# Spindle.net
KiCad netlist of a schematic drawn in Altium Designer
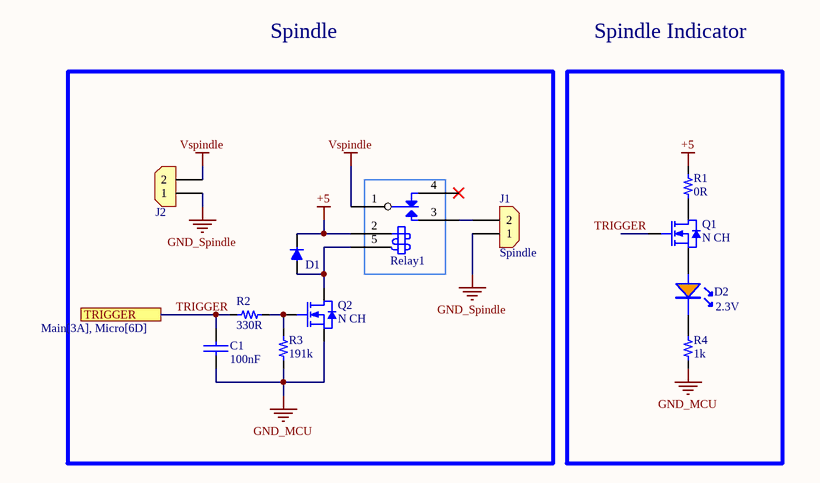
[diagram p0: Spindle.SchDoc]

(export (version "E")
  (design (tool "Eeschema 10.0.6"))
  (components
    (comp (ref "C1")
      (value "100nF")
      (footprint "0603_cap")
      (description "50V 100nF X7R ±10% 0603 Ceramic Capacitors RoHS")
      (fields
        (field (name "MANUFACTURER") "FOJAN")
        (field (name "MANUFACTURER PART NUMBER") "FCC0603B104K500CT")
      )
      (libsource (lib "CNCLib") (part "Cap_100nF_0603_50V"))
    )
    (comp (ref "D1")
      (value "DIODE STANDARD 50V 1A SOD-123F")
      (footprint "SOD-123FL_MCC")
      (description "25A Independent 50V 1.1V@1A 1A SOD-123F Single Diodes RoHS")
      (fields (field (name "MANUFACTURER") "YONGYUTAI") (field (name "MANUFACTURER PART NUMBER") "1N4001W"))
      (libsource (lib "CNCLib") (part "Diode 1N4001W"))
    )
    (comp (ref "D2")
      (value "2.3V")
      (footprint "0805_LED")
      (description "LED ORANGE WATER CLEAR 0805 SMD")
      (fields
        (field (name "MANUFACTURER") "XINGLIGHT")
        (field (name "MANUFACTURER PART NUMBER") "XL-2012UOC")
      )
      (libsource (lib "CNCLib") (part "LED_0805_Orange"))
    )
    (comp (ref "J1")
      (value "Connector 2pos")
      (footprint "CON_2x1_TH_5MM")
      (description "2POS 5MM")
      (fields (field (name "MANUFACTURER") "JILN") (field (name "MANUFACTURER PART NUMBER") "JL126-50002G01"))
      (libsource (lib "CNCLib") (part "Con_2x1_TH_5mm"))
    )
    (comp (ref "J2")
      (value "Connector 2pos")
      (footprint "CON_2x1_TH_5MM")
      (description "2POS 5MM")
      (fields (field (name "MANUFACTURER") "JILN") (field (name "MANUFACTURER PART NUMBER") "JL126-50002G01"))
      (libsource (lib "CNCLib") (part "Con_2x1_TH_5mm"))
    )
    (comp (ref "Q1")
      (value "N CH")
      (footprint "SOT_23_3")
      (description "MOSFET N-CH 50V 200mA SOT-23")
      (fields (field (name "MANUFACTURER") "onsemi") (field (name "MANUFACTURER PART NUMBER") "BSS138LT1G"))
      (libsource (lib "CNCLib") (part "Q_NFET_50V_200mA_SOT23"))
    )
    (comp (ref "Q2")
      (value "N CH")
      (footprint "SOT_23_3")
      (description "MOSFET N-CH 20V SOT23")
      (fields (field (name "MANUFACTURER") "Doeshare") (field (name "MANUFACTURER PART NUMBER") "DN2302S"))
      (libsource (lib "CNCLib") (part "Q_NFET_20V_3.2A_SOT23"))
    )
    (comp (ref "R1")
      (value "0R")
      (footprint "0603_res")
      (description "RES SMD 0R OHM 5% 1/10W 0603")
      (fields
        (field (name "MANUFACTURER") "FOJAN")
        (field (name "MANUFACTURER PART NUMBER") "FRC0603P000 TS")
      )
      (libsource (lib "CNCLib") (part "Res_0R_0603_1/10W"))
    )
    (comp (ref "R2")
      (value "330R")
      (footprint "0603_res")
      (description "RES SMD 330R OHM 5% 1/10W 0603")
      (fields
        (field (name "MANUFACTURER") "FOJAN")
        (field (name "MANUFACTURER PART NUMBER") "FRC0603J331 TS")
      )
      (libsource (lib "CNCLib") (part "Res_330R_0603_1/10W"))
    )
    (comp (ref "R3")
      (value "191k")
      (footprint "0603_res")
      (description "100mW Thick Film Resistor 75V ±100ppm/℃ ±1% 191kΩ 0603 Chip Resistor - Surface Mount ROHS")
      (fields
        (field (name "MANUFACTURER") "YAGEO")
        (field (name "MANUFACTURER PART NUMBER") "AC0603FR-07191KL")
      )
      (libsource (lib "CNCLib") (part "Res_191k_0603_1/10W"))
    )
    (comp (ref "R4")
      (value "1k")
      (footprint "0603_res")
      (description "RES SMD 1k OHM 5% 1/10W 0603")
      (fields
        (field (name "MANUFACTURER") "FOJAN")
        (field (name "MANUFACTURER PART NUMBER") "FRC0603J102 TS")
      )
      (libsource (lib "CNCLib") (part "Res_1k_0603_1/10W"))
    )
    (comp (ref "Relay1")
      (value "V_15A")
      (footprint "Relay_5V_15A")
      (description "250V@AC 5V 15A 1 Form C: 1C (SPDT-CO) Plugin,15.6x19.2mm Power Relays ROHS")
      (fields
        (field (name "MANUFACTURER") "Ningbo Songle Relay")
        (field (name "MANUFACTURER PART NUMBER") "SRD-05VDC-SL-C")
      )
      (libsource (lib "CNCLib") (part "Relay_5V_15A"))
    )
  )
  (nets
    (net (code "1") (name "+5") (class "Default")
      (node (ref "D1") (pin "2") (pinfunction "CATHODE_2") (pintype "passive"))
      (node (ref "R1") (pin "2") (pinfunction "2_2") (pintype "passive"))
      (node (ref "Relay1") (pin "2") (pinfunction "2_2") (pintype "passive"))
    )
    (net (code "2") (name "/TRIGGER") (class "Default")
      (node (ref "C1") (pin "1") (pinfunction "1_1") (pintype "passive"))
      (node (ref "Q1") (pin "1") (pinfunction "G_1") (pintype "passive"))
      (node (ref "R2") (pin "1") (pinfunction "1_1") (pintype "passive"))
    )
    (net (code "3") (name "GND_MCU") (class "Default")
      (node (ref "C1") (pin "2") (pinfunction "2_2") (pintype "passive"))
      (node (ref "Q2") (pin "2") (pinfunction "S_2") (pintype "passive"))
      (node (ref "R3") (pin "2") (pinfunction "2_2") (pintype "passive"))
      (node (ref "R4") (pin "1") (pinfunction "1_1") (pintype "passive"))
    )
    (net (code "4") (name "GND_Spindle") (class "Default")
      (node (ref "J1") (pin "1") (pinfunction "1_1") (pintype "passive"))
      (node (ref "J2") (pin "1") (pinfunction "1_1") (pintype "passive"))
    )
    (net (code "5") (name "Net-(D1-ANODE)") (class "Default")
      (node (ref "D1") (pin "1") (pinfunction "ANODE_1") (pintype "passive"))
      (node (ref "Q2") (pin "3") (pinfunction "D_3") (pintype "passive"))
      (node (ref "Relay1") (pin "5") (pinfunction "5_5") (pintype "passive"))
    )
    (net (code "6") (name "Net-(D2-A)") (class "Default")
      (node (ref "D2") (pin "1") (pinfunction "A_1") (pintype "passive"))
      (node (ref "Q1") (pin "2") (pinfunction "S_2") (pintype "passive"))
    )
    (net (code "7") (name "Net-(D2-Pad2)") (class "Default")
      (node (ref "D2") (pin "2") (pinfunction "2_2") (pintype "passive"))
      (node (ref "R4") (pin "2") (pinfunction "2_2") (pintype "passive"))
    )
    (net (code "8") (name "Net-(J1-Pad2)") (class "Default")
      (node (ref "J1") (pin "2") (pinfunction "2_2") (pintype "passive"))
      (node (ref "Relay1") (pin "3") (pinfunction "3_3") (pintype "passive"))
    )
    (net (code "9") (name "Net-(Q1-D)") (class "Default")
      (node (ref "Q1") (pin "3") (pinfunction "D_3") (pintype "passive"))
      (node (ref "R1") (pin "1") (pinfunction "1_1") (pintype "passive"))
    )
    (net (code "10") (name "Net-(Q2-G)") (class "Default")
      (node (ref "Q2") (pin "1") (pinfunction "G_1") (pintype "passive"))
      (node (ref "R2") (pin "2") (pinfunction "2_2") (pintype "passive"))
      (node (ref "R3") (pin "1") (pinfunction "1_1") (pintype "passive"))
    )
    (net (code "11") (name "Vspindle") (class "Default")
      (node (ref "J2") (pin "2") (pinfunction "2_2") (pintype "passive"))
      (node (ref "Relay1") (pin "1") (pinfunction "1_1") (pintype "passive"))
    )
    (net (code "12") (name "unconnected-(Relay1-Pad4)") (class "Default")
      (node (ref "Relay1") (pin "4") (pinfunction "4_4") (pintype "passive+no_connect"))
    )
  )
)
